# servo_mp3.net
KiCad netlist of a schematic drawn in EAGLE
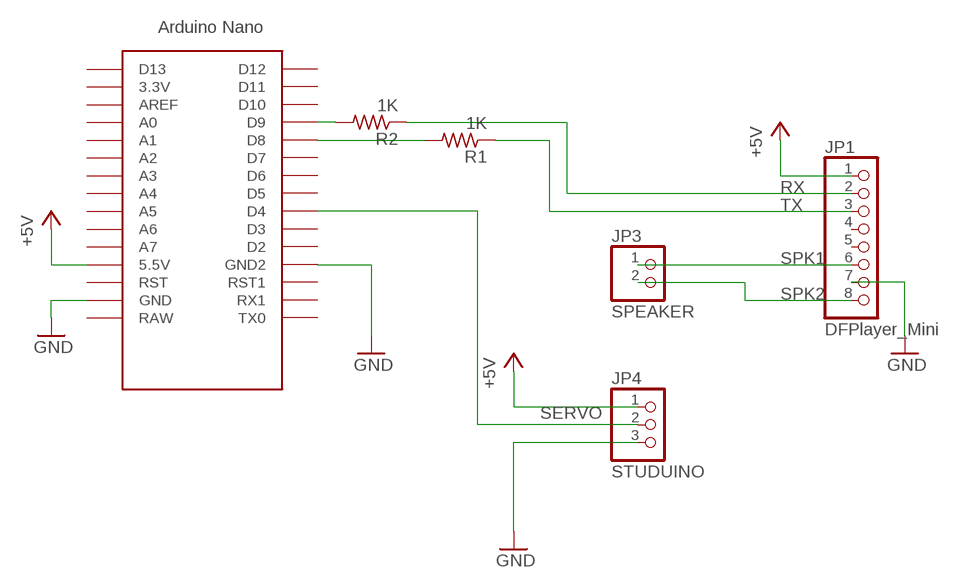
[diagram p0: schematic, sheet 1]

(export (version "E")
  (design (tool "Eeschema 10.0.6"))
  (components
    (comp (ref "JP1")
      (value "DFPlayer_Mini")
      (footprint "eagle-import:1X08")
      (libsource (lib "eagle-import") (part "PINHD-1X8"))
    )
    (comp (ref "JP3")
      (value "SPEAKER")
      (footprint "eagle-import:1X02")
      (libsource (lib "eagle-import") (part "PINHD-1X2"))
    )
    (comp (ref "JP4")
      (value "STUDUINO")
      (footprint "eagle-import:1X03")
      (libsource (lib "eagle-import") (part "PINHD-1X3"))
    )
    (comp (ref "R1")
      (value "1K")
      (footprint "eagle-import:0207_12")
      (libsource (lib "eagle-import") (part "R-US_0207/12"))
    )
    (comp (ref "R2")
      (value "1K")
      (footprint "eagle-import:0207_12")
      (libsource (lib "eagle-import") (part "R-US_0207/12"))
    )
    (comp (ref "U$1")
      (value "NANO")
      (footprint "eagle-import:NANO")
      (libsource (lib "eagle-import") (part "NANO"))
    )
  )
  (nets
    (net (code "1") (name "+5V") (class "Default")
      (node (ref "JP1") (pin "1") (pinfunction "1_1") (pintype "passive"))
      (node (ref "JP4") (pin "1") (pinfunction "1_1") (pintype "passive"))
      (node (ref "U$1") (pin "5V") (pinfunction "5.5V_5V") (pintype "bidirectional"))
    )
    (net (code "2") (name "/RX") (class "Default")
      (node (ref "JP1") (pin "2") (pinfunction "2_2") (pintype "passive"))
      (node (ref "R2") (pin "1") (pinfunction "1_1") (pintype "passive"))
    )
    (net (code "3") (name "/SERVO") (class "Default")
      (node (ref "JP4") (pin "2") (pinfunction "2_2") (pintype "passive"))
      (node (ref "U$1") (pin "D4") (pinfunction "D4_D4") (pintype "bidirectional"))
    )
    (net (code "4") (name "/SPK1") (class "Default")
      (node (ref "JP1") (pin "6") (pinfunction "6_6") (pintype "passive"))
      (node (ref "JP3") (pin "1") (pinfunction "1_1") (pintype "passive"))
    )
    (net (code "5") (name "/SPK2") (class "Default")
      (node (ref "JP1") (pin "8") (pinfunction "8_8") (pintype "passive"))
      (node (ref "JP3") (pin "2") (pinfunction "2_2") (pintype "passive"))
    )
    (net (code "6") (name "/TX") (class "Default")
      (node (ref "JP1") (pin "3") (pinfunction "3_3") (pintype "passive"))
      (node (ref "R1") (pin "1") (pinfunction "1_1") (pintype "passive"))
    )
    (net (code "7") (name "GND") (class "Default")
      (node (ref "JP1") (pin "7") (pinfunction "7_7") (pintype "passive"))
      (node (ref "JP4") (pin "3") (pinfunction "3_3") (pintype "passive"))
      (node (ref "U$1") (pin "GND") (pinfunction "GND_GND") (pintype "bidirectional"))
      (node (ref "U$1") (pin "GND1") (pinfunction "GND2_GND1") (pintype "bidirectional"))
    )
    (net (code "8") (name "Net-(R1-Pad2)") (class "Default")
      (node (ref "R1") (pin "2") (pinfunction "2_2") (pintype "passive"))
      (node (ref "U$1") (pin "D8") (pinfunction "D8_D8") (pintype "bidirectional"))
    )
    (net (code "9") (name "Net-(R2-Pad2)") (class "Default")
      (node (ref "R2") (pin "2") (pinfunction "2_2") (pintype "passive"))
      (node (ref "U$1") (pin "D9") (pinfunction "D9_D9") (pintype "bidirectional"))
    )
    (net (code "10") (name "unconnected-(JP1-Pad4)") (class "Default")
      (node (ref "JP1") (pin "4") (pinfunction "4_4") (pintype "passive"))
    )
    (net (code "11") (name "unconnected-(JP1-Pad5)") (class "Default")
      (node (ref "JP1") (pin "5") (pinfunction "5_5") (pintype "passive"))
    )
    (net (code "12") (name "unconnected-(U$1-Pad3.3V)") (class "Default")
      (node (ref "U$1") (pin "3.3V") (pinfunction "3.3V_3.3V") (pintype "bidirectional"))
    )
    (net (code "13") (name "unconnected-(U$1-PadA0)") (class "Default")
      (node (ref "U$1") (pin "A0") (pinfunction "A0_A0") (pintype "bidirectional"))
    )
    (net (code "14") (name "unconnected-(U$1-PadA1)") (class "Default")
      (node (ref "U$1") (pin "A1") (pinfunction "A1_A1") (pintype "bidirectional"))
    )
    (net (code "15") (name "unconnected-(U$1-PadA2)") (class "Default")
      (node (ref "U$1") (pin "A2") (pinfunction "A2_A2") (pintype "bidirectional"))
    )
    (net (code "16") (name "unconnected-(U$1-PadA3)") (class "Default")
      (node (ref "U$1") (pin "A3") (pinfunction "A3_A3") (pintype "bidirectional"))
    )
    (net (code "17") (name "unconnected-(U$1-PadA4)") (class "Default")
      (node (ref "U$1") (pin "A4") (pinfunction "A4_A4") (pintype "bidirectional"))
    )
    (net (code "18") (name "unconnected-(U$1-PadA5)") (class "Default")
      (node (ref "U$1") (pin "A5") (pinfunction "A5_A5") (pintype "bidirectional"))
    )
    (net (code "19") (name "unconnected-(U$1-PadA6)") (class "Default")
      (node (ref "U$1") (pin "A6") (pinfunction "A6_A6") (pintype "bidirectional"))
    )
    (net (code "20") (name "unconnected-(U$1-PadA7)") (class "Default")
      (node (ref "U$1") (pin "A7") (pinfunction "A7_A7") (pintype "bidirectional"))
    )
    (net (code "21") (name "unconnected-(U$1-PadAREF)") (class "Default")
      (node (ref "U$1") (pin "AREF") (pinfunction "AREF_AREF") (pintype "bidirectional"))
    )
    (net (code "22") (name "unconnected-(U$1-PadD2)") (class "Default")
      (node (ref "U$1") (pin "D2") (pinfunction "D2_D2") (pintype "bidirectional"))
    )
    (net (code "23") (name "unconnected-(U$1-PadD3)") (class "Default")
      (node (ref "U$1") (pin "D3") (pinfunction "D3_D3") (pintype "bidirectional"))
    )
    (net (code "24") (name "unconnected-(U$1-PadD5)") (class "Default")
      (node (ref "U$1") (pin "D5") (pinfunction "D5_D5") (pintype "bidirectional"))
    )
    (net (code "25") (name "unconnected-(U$1-PadD6)") (class "Default")
      (node (ref "U$1") (pin "D6") (pinfunction "D6_D6") (pintype "bidirectional"))
    )
    (net (code "26") (name "unconnected-(U$1-PadD7)") (class "Default")
      (node (ref "U$1") (pin "D7") (pinfunction "D7_D7") (pintype "bidirectional"))
    )
    (net (code "27") (name "unconnected-(U$1-PadD10)") (class "Default")
      (node (ref "U$1") (pin "D10") (pinfunction "D10_D10") (pintype "bidirectional"))
    )
    (net (code "28") (name "unconnected-(U$1-PadD11)") (class "Default")
      (node (ref "U$1") (pin "D11") (pinfunction "D11_D11") (pintype "bidirectional"))
    )
    (net (code "29") (name "unconnected-(U$1-PadD12)") (class "Default")
      (node (ref "U$1") (pin "D12") (pinfunction "D12_D12") (pintype "bidirectional"))
    )
    (net (code "30") (name "unconnected-(U$1-PadD13)") (class "Default")
      (node (ref "U$1") (pin "D13") (pinfunction "D13_D13") (pintype "bidirectional"))
    )
    (net (code "31") (name "unconnected-(U$1-PadICSP1)") (class "Default")
      (node (ref "U$1") (pin "ICSP1") (pinfunction "ICSP1_ICSP1") (pintype "bidirectional"))
    )
    (net (code "32") (name "unconnected-(U$1-PadICSP2)") (class "Default")
      (node (ref "U$1") (pin "ICSP2") (pinfunction "ICSP2_ICSP2") (pintype "bidirectional"))
    )
    (net (code "33") (name "unconnected-(U$1-PadICSP3)") (class "Default")
      (node (ref "U$1") (pin "ICSP3") (pinfunction "ICSP3_ICSP3") (pintype "bidirectional"))
    )
    (net (code "34") (name "unconnected-(U$1-PadICSP4)") (class "Default")
      (node (ref "U$1") (pin "ICSP4") (pinfunction "ICSP4_ICSP4") (pintype "bidirectional"))
    )
    (net (code "35") (name "unconnected-(U$1-PadICSP5)") (class "Default")
      (node (ref "U$1") (pin "ICSP5") (pinfunction "ICSP5_ICSP5") (pintype "bidirectional"))
    )
    (net (code "36") (name "unconnected-(U$1-PadICSP6)") (class "Default")
      (node (ref "U$1") (pin "ICSP6") (pinfunction "ICSP6_ICSP6") (pintype "bidirectional"))
    )
    (net (code "37") (name "unconnected-(U$1-PadRAW)") (class "Default")
      (node (ref "U$1") (pin "RAW") (pinfunction "RAW_RAW") (pintype "bidirectional"))
    )
    (net (code "38") (name "unconnected-(U$1-PadRST)") (class "Default")
      (node (ref "U$1") (pin "RST") (pinfunction "RST_RST") (pintype "bidirectional"))
    )
    (net (code "39") (name "unconnected-(U$1-PadRST1)") (class "Default")
      (node (ref "U$1") (pin "RST1") (pinfunction "RST1_RST1") (pintype "bidirectional"))
    )
    (net (code "40") (name "unconnected-(U$1-PadRX1)") (class "Default")
      (node (ref "U$1") (pin "RX1") (pinfunction "RX1_RX1") (pintype "bidirectional"))
    )
    (net (code "41") (name "unconnected-(U$1-PadTX0)") (class "Default")
      (node (ref "U$1") (pin "TX0") (pinfunction "TX0_TX0") (pintype "bidirectional"))
    )
  )
)
